# shupito.net
KiCad netlist of a schematic drawn in EAGLE
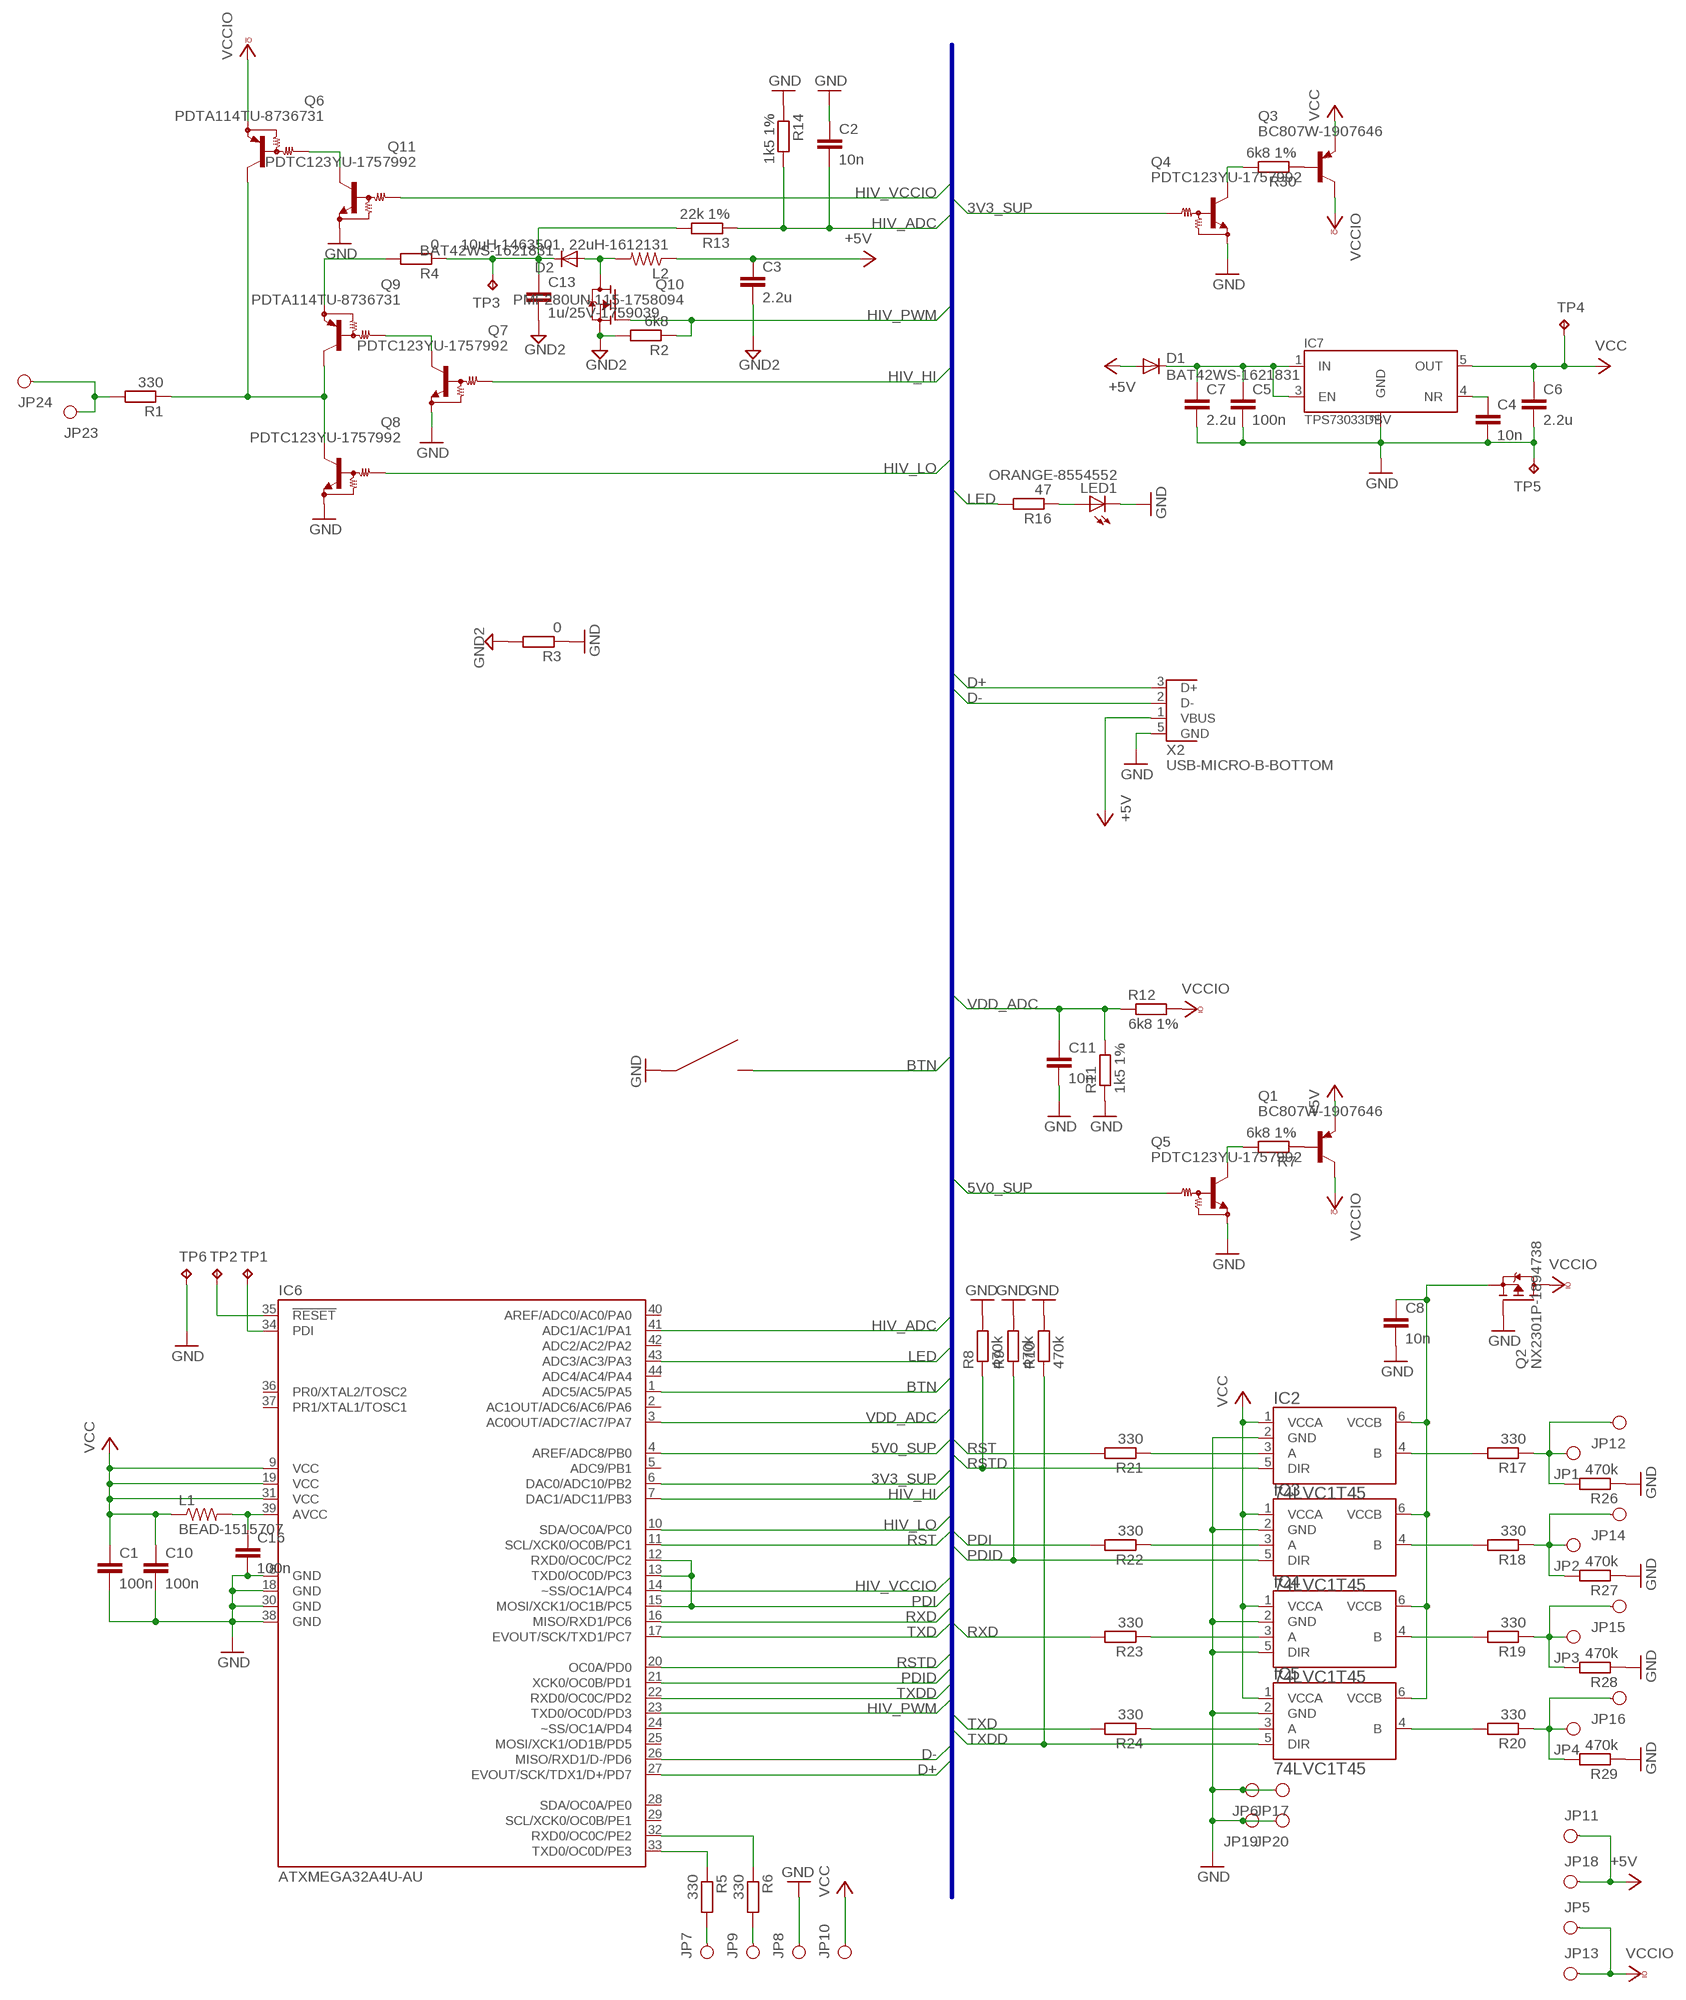
[diagram p0: schematic, sheet 1]

(export (version "E")
  (design (tool "Eeschema 10.0.6"))
  (components
    (comp (ref "C1")
      (value "100n")
      (footprint "eagle-import:C0603K")
      (libsource (lib "eagle-import") (part "C-EUC0603K"))
    )
    (comp (ref "C2")
      (value "10n")
      (footprint "eagle-import:C0603K")
      (libsource (lib "eagle-import") (part "C-EUC0603K"))
    )
    (comp (ref "C3")
      (value "2.2u")
      (footprint "eagle-import:C0603K")
      (libsource (lib "eagle-import") (part "C-EUC0603K"))
    )
    (comp (ref "C4")
      (value "10n")
      (footprint "eagle-import:C0603K")
      (libsource (lib "eagle-import") (part "C-EUC0603K"))
    )
    (comp (ref "C5")
      (value "100n")
      (footprint "eagle-import:C0603K")
      (libsource (lib "eagle-import") (part "C-EUC0603K"))
    )
    (comp (ref "C6")
      (value "2.2u")
      (footprint "eagle-import:C0603K")
      (libsource (lib "eagle-import") (part "C-EUC0603K"))
    )
    (comp (ref "C7")
      (value "2.2u")
      (footprint "eagle-import:C0603K")
      (libsource (lib "eagle-import") (part "C-EUC0603K"))
    )
    (comp (ref "C8")
      (value "10n")
      (footprint "eagle-import:C0603K")
      (libsource (lib "eagle-import") (part "C-EUC0603K"))
    )
    (comp (ref "C10")
      (value "100n")
      (footprint "eagle-import:C0603K")
      (libsource (lib "eagle-import") (part "C-EUC0603K"))
    )
    (comp (ref "C11")
      (value "10n")
      (footprint "eagle-import:C0603K")
      (libsource (lib "eagle-import") (part "C-EUC0603K"))
    )
    (comp (ref "C13")
      (value "1u/25V-1759039")
      (footprint "eagle-import:C0603K")
      (libsource (lib "eagle-import") (part "C-EUC0603K"))
    )
    (comp (ref "C16")
      (value "100n")
      (footprint "eagle-import:C0603K")
      (libsource (lib "eagle-import") (part "C-EUC0603K"))
    )
    (comp (ref "D1")
      (value "BAT42WS-1621831")
      (footprint "eagle-import:SOD323")
      (libsource (lib "eagle-import") (part "DIODE-SOD323"))
    )
    (comp (ref "D2")
      (value "BAT42WS-1621831")
      (footprint "eagle-import:SOD323")
      (libsource (lib "eagle-import") (part "DIODE-SOD323"))
    )
    (comp (ref "IC2")
      (value "74LVC1T45")
      (footprint "eagle-import:SOT236")
      (libsource (lib "eagle-import") (part "741T45DBVLVC"))
    )
    (comp (ref "IC3")
      (value "74LVC1T45")
      (footprint "eagle-import:SOT236")
      (libsource (lib "eagle-import") (part "741T45DBVLVC"))
    )
    (comp (ref "IC4")
      (value "74LVC1T45")
      (footprint "eagle-import:SOT236")
      (libsource (lib "eagle-import") (part "741T45DBVLVC"))
    )
    (comp (ref "IC5")
      (value "74LVC1T45")
      (footprint "eagle-import:SOT236")
      (libsource (lib "eagle-import") (part "741T45DBVLVC"))
    )
    (comp (ref "IC6")
      (value "ATXMEGA32A4U-AU")
      (footprint "eagle-import:TQFP44")
      (libsource (lib "eagle-import") (part "ATXMEGAA4U-AU32"))
    )
    (comp (ref "IC7")
      (value "TPS73033DBV")
      (footprint "eagle-import:SOT23-DBV")
      (libsource (lib "eagle-import") (part "TPS73033DBV"))
    )
    (comp (ref "JP1")
      (value "PINH1X01SMD")
      (footprint "eagle-import:PINH1X01SMD")
      (libsource (lib "eagle-import") (part "PINH1X01SMD"))
    )
    (comp (ref "JP2")
      (value "PINH1X01SMD")
      (footprint "eagle-import:PINH1X01SMD")
      (libsource (lib "eagle-import") (part "PINH1X01SMD"))
    )
    (comp (ref "JP3")
      (value "PINH1X01SMD")
      (footprint "eagle-import:PINH1X01SMD")
      (libsource (lib "eagle-import") (part "PINH1X01SMD"))
    )
    (comp (ref "JP4")
      (value "PINH1X01SMD")
      (footprint "eagle-import:PINH1X01SMD")
      (libsource (lib "eagle-import") (part "PINH1X01SMD"))
    )
    (comp (ref "JP5")
      (value "PINH1X01SMD")
      (footprint "eagle-import:PINH1X01SMD")
      (libsource (lib "eagle-import") (part "PINH1X01SMD"))
    )
    (comp (ref "JP6")
      (value "PINH1X01SMD")
      (footprint "eagle-import:PINH1X01SMD")
      (libsource (lib "eagle-import") (part "PINH1X01SMD"))
    )
    (comp (ref "JP7")
      (value "PINH1X01SMD")
      (footprint "eagle-import:PINH1X01SMD")
      (libsource (lib "eagle-import") (part "PINH1X01SMD"))
    )
    (comp (ref "JP8")
      (value "PINH1X01SMD")
      (footprint "eagle-import:PINH1X01SMD")
      (libsource (lib "eagle-import") (part "PINH1X01SMD"))
    )
    (comp (ref "JP9")
      (value "PINH1X01SMD")
      (footprint "eagle-import:PINH1X01SMD")
      (libsource (lib "eagle-import") (part "PINH1X01SMD"))
    )
    (comp (ref "JP10")
      (value "PINH1X01SMD")
      (footprint "eagle-import:PINH1X01SMD")
      (libsource (lib "eagle-import") (part "PINH1X01SMD"))
    )
    (comp (ref "JP11")
      (value "PINH1X01SMD")
      (footprint "eagle-import:PINH1X01SMD")
      (libsource (lib "eagle-import") (part "PINH1X01SMD"))
    )
    (comp (ref "JP12")
      (value "PINH1X01SMD")
      (footprint "eagle-import:PINH1X01SMD")
      (libsource (lib "eagle-import") (part "PINH1X01SMD"))
    )
    (comp (ref "JP13")
      (value "PINH1X01SMD")
      (footprint "eagle-import:PINH1X01SMD")
      (libsource (lib "eagle-import") (part "PINH1X01SMD"))
    )
    (comp (ref "JP14")
      (value "PINH1X01SMD")
      (footprint "eagle-import:PINH1X01SMD")
      (libsource (lib "eagle-import") (part "PINH1X01SMD"))
    )
    (comp (ref "JP15")
      (value "PINH1X01SMD")
      (footprint "eagle-import:PINH1X01SMD")
      (libsource (lib "eagle-import") (part "PINH1X01SMD"))
    )
    (comp (ref "JP16")
      (value "PINH1X01SMD")
      (footprint "eagle-import:PINH1X01SMD")
      (libsource (lib "eagle-import") (part "PINH1X01SMD"))
    )
    (comp (ref "JP17")
      (value "PINH1X01SMD")
      (footprint "eagle-import:PINH1X01SMD")
      (libsource (lib "eagle-import") (part "PINH1X01SMD"))
    )
    (comp (ref "JP18")
      (value "PINH1X01SMD")
      (footprint "eagle-import:PINH1X01SMD")
      (libsource (lib "eagle-import") (part "PINH1X01SMD"))
    )
    (comp (ref "JP19")
      (value "PINH1X01SMD")
      (footprint "eagle-import:PINH1X01SMD")
      (libsource (lib "eagle-import") (part "PINH1X01SMD"))
    )
    (comp (ref "JP20")
      (value "PINH1X01SMD")
      (footprint "eagle-import:PINH1X01SMD")
      (libsource (lib "eagle-import") (part "PINH1X01SMD"))
    )
    (comp (ref "JP23")
      (value "PINH1X01SMD")
      (footprint "eagle-import:PINH1X01SMD")
      (libsource (lib "eagle-import") (part "PINH1X01SMD"))
    )
    (comp (ref "JP24")
      (value "PINH1X01SMD")
      (footprint "eagle-import:PINH1X01SMD")
      (libsource (lib "eagle-import") (part "PINH1X01SMD"))
    )
    (comp (ref "L1")
      (value "BEAD-1515707")
      (footprint "eagle-import:R0603")
      (libsource (lib "eagle-import") (part "R-US_R0603"))
    )
    (comp (ref "L2")
      (value "10uH-1463501, 22uH-1612131")
      (footprint "eagle-import:R0805")
      (libsource (lib "eagle-import") (part "R-US_R0805"))
    )
    (comp (ref "LED1")
      (value "ORANGE-8554552")
      (footprint "eagle-import:CHIPLED_0603")
      (libsource (lib "eagle-import") (part "LEDCHIPLED_0603"))
    )
    (comp (ref "Q1")
      (value "BC807W-1907646")
      (footprint "eagle-import:SOT323-BEC")
      (libsource (lib "eagle-import") (part "BC807W"))
    )
    (comp (ref "Q2")
      (value "NX2301P-1894738")
      (footprint "eagle-import:SOT23")
      (libsource (lib "eagle-import") (part "P-MOSFET-SOT23-GSD"))
    )
    (comp (ref "Q3")
      (value "BC807W-1907646")
      (footprint "eagle-import:SOT323-BEC")
      (libsource (lib "eagle-import") (part "BC807W"))
    )
    (comp (ref "Q4")
      (value "PDTC123YU-1757992")
      (footprint "eagle-import:SOT323")
      (libsource (lib "eagle-import") (part "NPN-BIAS-SOT323-BEC"))
    )
    (comp (ref "Q5")
      (value "PDTC123YU-1757992")
      (footprint "eagle-import:SOT323")
      (libsource (lib "eagle-import") (part "NPN-BIAS-SOT323-BEC"))
    )
    (comp (ref "Q6")
      (value "PDTA114TU-8736731")
      (footprint "eagle-import:SOT323")
      (libsource (lib "eagle-import") (part "PNP-BIAS-SOT323-BEC"))
    )
    (comp (ref "Q7")
      (value "PDTC123YU-1757992")
      (footprint "eagle-import:SOT323")
      (libsource (lib "eagle-import") (part "NPN-BIAS-SOT323-BEC"))
    )
    (comp (ref "Q8")
      (value "PDTC123YU-1757992")
      (footprint "eagle-import:SOT323")
      (libsource (lib "eagle-import") (part "NPN-BIAS-SOT323-BEC"))
    )
    (comp (ref "Q9")
      (value "PDTA114TU-8736731")
      (footprint "eagle-import:SOT323")
      (libsource (lib "eagle-import") (part "PNP-BIAS-SOT323-BEC"))
    )
    (comp (ref "Q10")
      (value "PMF280UN,115-1758094")
      (footprint "eagle-import:SOT323")
      (libsource (lib "eagle-import") (part "N-MOSFET-SOT323-GSD"))
    )
    (comp (ref "Q11")
      (value "PDTC123YU-1757992")
      (footprint "eagle-import:SOT323")
      (libsource (lib "eagle-import") (part "NPN-BIAS-SOT323-BEC"))
    )
    (comp (ref "R1")
      (value "330")
      (footprint "eagle-import:R0603")
      (libsource (lib "eagle-import") (part "R-EU_R0603"))
    )
    (comp (ref "R2")
      (value "6k8")
      (footprint "eagle-import:R0603")
      (libsource (lib "eagle-import") (part "R-EU_R0603"))
    )
    (comp (ref "R3")
      (value "0")
      (footprint "eagle-import:R1206")
      (libsource (lib "eagle-import") (part "R-EU_R1206"))
    )
    (comp (ref "R4")
      (value "0")
      (footprint "eagle-import:R1206")
      (libsource (lib "eagle-import") (part "R-EU_R1206"))
    )
    (comp (ref "R5")
      (value "330")
      (footprint "eagle-import:R0603")
      (libsource (lib "eagle-import") (part "R-EU_R0603"))
    )
    (comp (ref "R6")
      (value "330")
      (footprint "eagle-import:R0603")
      (libsource (lib "eagle-import") (part "R-EU_R0603"))
    )
    (comp (ref "R7")
      (value "6k8 1%")
      (footprint "eagle-import:R0603")
      (libsource (lib "eagle-import") (part "R-EU_R0603"))
    )
    (comp (ref "R8")
      (value "470k")
      (footprint "eagle-import:R0603")
      (libsource (lib "eagle-import") (part "R-EU_R0603"))
    )
    (comp (ref "R9")
      (value "470k")
      (footprint "eagle-import:R0603")
      (libsource (lib "eagle-import") (part "R-EU_R0603"))
    )
    (comp (ref "R10")
      (value "470k")
      (footprint "eagle-import:R0603")
      (libsource (lib "eagle-import") (part "R-EU_R0603"))
    )
    (comp (ref "R11")
      (value "1k5 1%")
      (footprint "eagle-import:R0603")
      (libsource (lib "eagle-import") (part "R-EU_R0603"))
    )
    (comp (ref "R12")
      (value "6k8 1%")
      (footprint "eagle-import:R0603")
      (libsource (lib "eagle-import") (part "R-EU_R0603"))
    )
    (comp (ref "R13")
      (value "22k 1%")
      (footprint "eagle-import:R0603")
      (libsource (lib "eagle-import") (part "R-EU_R0603"))
    )
    (comp (ref "R14")
      (value "1k5 1%")
      (footprint "eagle-import:R0603")
      (libsource (lib "eagle-import") (part "R-EU_R0603"))
    )
    (comp (ref "R16")
      (value "47")
      (footprint "eagle-import:R0603")
      (libsource (lib "eagle-import") (part "R-EU_R0603"))
    )
    (comp (ref "R17")
      (value "330")
      (footprint "eagle-import:R0603")
      (libsource (lib "eagle-import") (part "R-EU_R0603"))
    )
    (comp (ref "R18")
      (value "330")
      (footprint "eagle-import:R0603")
      (libsource (lib "eagle-import") (part "R-EU_R0603"))
    )
    (comp (ref "R19")
      (value "330")
      (footprint "eagle-import:R0603")
      (libsource (lib "eagle-import") (part "R-EU_R0603"))
    )
    (comp (ref "R20")
      (value "330")
      (footprint "eagle-import:R0603")
      (libsource (lib "eagle-import") (part "R-EU_R0603"))
    )
    (comp (ref "R21")
      (value "330")
      (footprint "eagle-import:R0603")
      (libsource (lib "eagle-import") (part "R-EU_R0603"))
    )
    (comp (ref "R22")
      (value "330")
      (footprint "eagle-import:R0603")
      (libsource (lib "eagle-import") (part "R-EU_R0603"))
    )
    (comp (ref "R23")
      (value "330")
      (footprint "eagle-import:R0603")
      (libsource (lib "eagle-import") (part "R-EU_R0603"))
    )
    (comp (ref "R24")
      (value "330")
      (footprint "eagle-import:R0603")
      (libsource (lib "eagle-import") (part "R-EU_R0603"))
    )
    (comp (ref "R26")
      (value "470k")
      (footprint "eagle-import:R0603")
      (libsource (lib "eagle-import") (part "R-EU_R0603"))
    )
    (comp (ref "R27")
      (value "470k")
      (footprint "eagle-import:R0603")
      (libsource (lib "eagle-import") (part "R-EU_R0603"))
    )
    (comp (ref "R28")
      (value "470k")
      (footprint "eagle-import:R0603")
      (libsource (lib "eagle-import") (part "R-EU_R0603"))
    )
    (comp (ref "R29")
      (value "470k")
      (footprint "eagle-import:R0603")
      (libsource (lib "eagle-import") (part "R-EU_R0603"))
    )
    (comp (ref "R30")
      (value "6k8 1%")
      (footprint "eagle-import:R0603")
      (libsource (lib "eagle-import") (part "R-EU_R0603"))
    )
    (comp (ref "S1")
      (value "KSS241G")
      (footprint "eagle-import:KSS-G")
      (libsource (lib "eagle-import") (part "KSSG241"))
    )
    (comp (ref "TP1")
      (value "TPTP15SQ")
      (footprint "eagle-import:TP15SQ")
      (libsource (lib "eagle-import") (part "TPTP15SQ"))
    )
    (comp (ref "TP2")
      (value "TPTP15SQ")
      (footprint "eagle-import:TP15SQ")
      (libsource (lib "eagle-import") (part "TPTP15SQ"))
    )
    (comp (ref "TP3")
      (value "TPTP15SQ")
      (footprint "eagle-import:TP15SQ")
      (libsource (lib "eagle-import") (part "TPTP15SQ"))
    )
    (comp (ref "TP4")
      (value "TPTP15SQ")
      (footprint "eagle-import:TP15SQ")
      (libsource (lib "eagle-import") (part "TPTP15SQ"))
    )
    (comp (ref "TP5")
      (value "TPTP15SQ")
      (footprint "eagle-import:TP15SQ")
      (libsource (lib "eagle-import") (part "TPTP15SQ"))
    )
    (comp (ref "TP6")
      (value "TPTP15SQ")
      (footprint "eagle-import:TP15SQ")
      (libsource (lib "eagle-import") (part "TPTP15SQ"))
    )
    (comp (ref "X2")
      (value "USB-MICRO-B-BOTTOM")
      (footprint "eagle-import:USB-MICRO-B-BOTTOM-MOLEX")
      (libsource (lib "eagle-import") (part "USB-MICRO-B-BOTTOM"))
    )
  )
  (nets
    (net (code "1") (name "+5V") (class "Default")
      (node (ref "C3") (pin "1") (pinfunction "1_1") (pintype "passive"))
      (node (ref "D1") (pin "A") (pinfunction "A_A") (pintype "passive"))
      (node (ref "JP11") (pin "1") (pinfunction "1_1") (pintype "passive"))
      (node (ref "JP18") (pin "1") (pinfunction "1_1") (pintype "passive"))
      (node (ref "L2") (pin "1") (pinfunction "1_1") (pintype "passive"))
      (node (ref "Q1") (pin "2") (pinfunction "E_2") (pintype "passive"))
      (node (ref "X2") (pin "1") (pinfunction "VBUS_1") (pintype "passive"))
    )
    (net (code "2") (name "/3V3_SUP") (class "Default")
      (node (ref "IC6") (pin "6") (pinfunction "DAC0/ADC10/PB2_6") (pintype "bidirectional"))
      (node (ref "Q4") (pin "1") (pinfunction "B_1") (pintype "passive"))
    )
    (net (code "3") (name "/5V0_SUP") (class "Default")
      (node (ref "IC6") (pin "4") (pinfunction "AREF/ADC8/PB0_4") (pintype "bidirectional"))
      (node (ref "Q5") (pin "1") (pinfunction "B_1") (pintype "passive"))
    )
    (net (code "4") (name "/BTN") (class "Default")
      (node (ref "IC6") (pin "1") (pinfunction "ADC5/AC5/PA5_1") (pintype "bidirectional"))
      (node (ref "S1") (pin "2") (pinfunction "P$2_2") (pintype "passive"))
    )
    (net (code "5") (name "/D+") (class "Default")
      (node (ref "IC6") (pin "27") (pinfunction "EVOUT/SCK/TDX1/D+/PD7_27") (pintype "bidirectional"))
      (node (ref "X2") (pin "3") (pinfunction "D+_3") (pintype "bidirectional"))
    )
    (net (code "6") (name "/D-") (class "Default")
      (node (ref "IC6") (pin "26") (pinfunction "MISO/RXD1/D-/PD6_26") (pintype "bidirectional"))
      (node (ref "X2") (pin "2") (pinfunction "D-_2") (pintype "bidirectional"))
    )
    (net (code "7") (name "/HIV_ADC") (class "Default")
      (node (ref "C2") (pin "2") (pinfunction "2_2") (pintype "passive"))
      (node (ref "IC6") (pin "41") (pinfunction "ADC1/AC1/PA1_41") (pintype "bidirectional"))
      (node (ref "R13") (pin "1") (pinfunction "1_1") (pintype "passive"))
      (node (ref "R14") (pin "2") (pinfunction "2_2") (pintype "passive"))
    )
    (net (code "8") (name "/HIV_HI") (class "Default")
      (node (ref "IC6") (pin "7") (pinfunction "DAC1/ADC11/PB3_7") (pintype "bidirectional"))
      (node (ref "Q7") (pin "1") (pinfunction "B_1") (pintype "passive"))
    )
    (net (code "9") (name "/HIV_LO") (class "Default")
      (node (ref "IC6") (pin "10") (pinfunction "SDA/OC0A/PC0_10") (pintype "bidirectional"))
      (node (ref "Q8") (pin "1") (pinfunction "B_1") (pintype "passive"))
    )
    (net (code "10") (name "/HIV_PWM") (class "Default")
      (node (ref "IC6") (pin "23") (pinfunction "TXD0/OC0D/PD3_23") (pintype "bidirectional"))
      (node (ref "Q10") (pin "1") (pinfunction "G_1") (pintype "passive"))
      (node (ref "R2") (pin "1") (pinfunction "1_1") (pintype "passive"))
    )
    (net (code "11") (name "/HIV_VCCIO") (class "Default")
      (node (ref "IC6") (pin "14") (pinfunction "~{SS/OC1A/PC4}_14") (pintype "bidirectional"))
      (node (ref "Q11") (pin "1") (pinfunction "B_1") (pintype "passive"))
    )
    (net (code "12") (name "/LED") (class "Default")
      (node (ref "IC6") (pin "43") (pinfunction "ADC3/AC3/PA3_43") (pintype "bidirectional"))
      (node (ref "R16") (pin "2") (pinfunction "2_2") (pintype "passive"))
    )
    (net (code "13") (name "/PDI") (class "Default")
      (node (ref "IC6") (pin "12") (pinfunction "RXD0/OC0C/PC2_12") (pintype "bidirectional"))
      (node (ref "IC6") (pin "13") (pinfunction "TXD0/OC0D/PC3_13") (pintype "bidirectional"))
      (node (ref "IC6") (pin "15") (pinfunction "MOSI/XCK1/OC1B/PC5_15") (pintype "bidirectional"))
      (node (ref "R22") (pin "2") (pinfunction "2_2") (pintype "passive"))
    )
    (net (code "14") (name "/PDID") (class "Default")
      (node (ref "IC3") (pin "5") (pinfunction "DIR_5") (pintype "input"))
      (node (ref "IC6") (pin "21") (pinfunction "XCK0/OC0B/PD1_21") (pintype "bidirectional"))
      (node (ref "R9") (pin "1") (pinfunction "1_1") (pintype "passive"))
    )
    (net (code "15") (name "/RST") (class "Default")
      (node (ref "IC6") (pin "11") (pinfunction "SCL/XCK0/OC0B/PC1_11") (pintype "bidirectional"))
      (node (ref "R21") (pin "2") (pinfunction "2_2") (pintype "passive"))
    )
    (net (code "16") (name "/RSTD") (class "Default")
      (node (ref "IC2") (pin "5") (pinfunction "DIR_5") (pintype "input"))
      (node (ref "IC6") (pin "20") (pinfunction "OC0A/PD0_20") (pintype "bidirectional"))
      (node (ref "R8") (pin "1") (pinfunction "1_1") (pintype "passive"))
    )
    (net (code "17") (name "/RXD") (class "Default")
      (node (ref "IC6") (pin "16") (pinfunction "MISO/RXD1/PC6_16") (pintype "bidirectional"))
      (node (ref "R23") (pin "2") (pinfunction "2_2") (pintype "passive"))
    )
    (net (code "18") (name "/TXD") (class "Default")
      (node (ref "IC6") (pin "17") (pinfunction "EVOUT/SCK/TXD1/PC7_17") (pintype "bidirectional"))
      (node (ref "R24") (pin "2") (pinfunction "2_2") (pintype "passive"))
    )
    (net (code "19") (name "/TXDD") (class "Default")
      (node (ref "IC5") (pin "5") (pinfunction "DIR_5") (pintype "input"))
      (node (ref "IC6") (pin "22") (pinfunction "RXD0/OC0C/PD2_22") (pintype "bidirectional"))
      (node (ref "R10") (pin "1") (pinfunction "1_1") (pintype "passive"))
    )
    (net (code "20") (name "/VDD_ADC") (class "Default")
      (node (ref "C11") (pin "1") (pinfunction "1_1") (pintype "passive"))
      (node (ref "IC6") (pin "3") (pinfunction "AC0OUT/ADC7/AC7/PA7_3") (pintype "bidirectional"))
      (node (ref "R11") (pin "2") (pinfunction "2_2") (pintype "passive"))
      (node (ref "R12") (pin "1") (pinfunction "1_1") (pintype "passive"))
    )
    (net (code "21") (name "GND") (class "Default")
      (node (ref "C1") (pin "2") (pinfunction "2_2") (pintype "passive"))
      (node (ref "C10") (pin "2") (pinfunction "2_2") (pintype "passive"))
      (node (ref "C11") (pin "2") (pinfunction "2_2") (pintype "passive"))
      (node (ref "C16") (pin "2") (pinfunction "2_2") (pintype "passive"))
      (node (ref "C2") (pin "1") (pinfunction "1_1") (pintype "passive"))
      (node (ref "C4") (pin "2") (pinfunction "2_2") (pintype "passive"))
      (node (ref "C5") (pin "2") (pinfunction "2_2") (pintype "passive"))
      (node (ref "C6") (pin "2") (pinfunction "2_2") (pintype "passive"))
      (node (ref "C7") (pin "2") (pinfunction "2_2") (pintype "passive"))
      (node (ref "C8") (pin "2") (pinfunction "2_2") (pintype "passive"))
      (node (ref "IC2") (pin "2") (pinfunction "GND_2") (pintype "passive"))
      (node (ref "IC3") (pin "2") (pinfunction "GND_2") (pintype "passive"))
      (node (ref "IC4") (pin "2") (pinfunction "GND_2") (pintype "passive"))
      (node (ref "IC4") (pin "5") (pinfunction "DIR_5") (pintype "input"))
      (node (ref "IC5") (pin "2") (pinfunction "GND_2") (pintype "passive"))
      (node (ref "IC6") (pin "18") (pinfunction "GND_18") (pintype "passive"))
      (node (ref "IC6") (pin "30") (pinfunction "GND_30") (pintype "passive"))
      (node (ref "IC6") (pin "38") (pinfunction "GND_38") (pintype "passive"))
      (node (ref "IC6") (pin "8") (pinfunction "GND_8") (pintype "passive"))
      (node (ref "IC7") (pin "2") (pinfunction "GND_2") (pintype "passive"))
      (node (ref "JP17") (pin "1") (pinfunction "1_1") (pintype "passive"))
      (node (ref "JP19") (pin "1") (pinfunction "1_1") (pintype "passive"))
      (node (ref "JP20") (pin "1") (pinfunction "1_1") (pintype "passive"))
      (node (ref "JP6") (pin "1") (pinfunction "1_1") (pintype "passive"))
      (node (ref "JP8") (pin "1") (pinfunction "1_1") (pintype "passive"))
      (node (ref "LED1") (pin "C") (pinfunction "C_C") (pintype "passive"))
      (node (ref "Q11") (pin "2") (pinfunction "E_2") (pintype "passive"))
      (node (ref "Q2") (pin "1") (pinfunction "G_1") (pintype "passive"))
      (node (ref "Q4") (pin "2") (pinfunction "E_2") (pintype "passive"))
      (node (ref "Q5") (pin "2") (pinfunction "E_2") (pintype "passive"))
      (node (ref "Q7") (pin "2") (pinfunction "E_2") (pintype "passive"))
      (node (ref "Q8") (pin "2") (pinfunction "E_2") (pintype "passive"))
      (node (ref "R10") (pin "2") (pinfunction "2_2") (pintype "passive"))
      (node (ref "R11") (pin "1") (pinfunction "1_1") (pintype "passive"))
      (node (ref "R14") (pin "1") (pinfunction "1_1") (pintype "passive"))
      (node (ref "R26") (pin "1") (pinfunction "1_1") (pintype "passive"))
      (node (ref "R27") (pin "1") (pinfunction "1_1") (pintype "passive"))
      (node (ref "R28") (pin "1") (pinfunction "1_1") (pintype "passive"))
      (node (ref "R29") (pin "1") (pinfunction "1_1") (pintype "passive"))
      (node (ref "R3") (pin "1") (pinfunction "1_1") (pintype "passive"))
      (node (ref "R8") (pin "2") (pinfunction "2_2") (pintype "passive"))
      (node (ref "R9") (pin "2") (pinfunction "2_2") (pintype "passive"))
      (node (ref "S1") (pin "1") (pinfunction "P$1_1") (pintype "passive"))
      (node (ref "TP5") (pin "TP") (pinfunction "TP_TP") (pintype "input"))
      (node (ref "TP6") (pin "TP") (pinfunction "TP_TP") (pintype "input"))
      (node (ref "X2") (pin "5") (pinfunction "GND_5") (pintype "passive"))
    )
    (net (code "22") (name "GND2") (class "Default")
      (node (ref "C13") (pin "2") (pinfunction "2_2") (pintype "passive"))
      (node (ref "C3") (pin "2") (pinfunction "2_2") (pintype "passive"))
      (node (ref "Q10") (pin "2") (pinfunction "S_2") (pintype "passive"))
      (node (ref "R2") (pin "2") (pinfunction "2_2") (pintype "passive"))
      (node (ref "R3") (pin "2") (pinfunction "2_2") (pintype "passive"))
    )
    (net (code "23") (name "Net-(C13-Pad1)") (class "Default")
      (node (ref "C13") (pin "1") (pinfunction "1_1") (pintype "passive"))
      (node (ref "D2") (pin "C") (pinfunction "C_C") (pintype "passive"))
      (node (ref "R13") (pin "2") (pinfunction "2_2") (pintype "passive"))
      (node (ref "R4") (pin "1") (pinfunction "1_1") (pintype "passive"))
      (node (ref "TP3") (pin "TP") (pinfunction "TP_TP") (pintype "input"))
    )
    (net (code "24") (name "Net-(IC2-A)") (class "Default")
      (node (ref "IC2") (pin "3") (pinfunction "A_3") (pintype "bidirectional"))
      (node (ref "R21") (pin "1") (pinfunction "1_1") (pintype "passive"))
    )
    (net (code "25") (name "Net-(IC2-B)") (class "Default")
      (node (ref "IC2") (pin "4") (pinfunction "B_4") (pintype "bidirectional"))
      (node (ref "R17") (pin "2") (pinfunction "2_2") (pintype "passive"))
    )
    (net (code "26") (name "Net-(IC2-VCCB)") (class "Default")
      (node (ref "C8") (pin "1") (pinfunction "1_1") (pintype "passive"))
      (node (ref "IC2") (pin "6") (pinfunction "VCCB_6") (pintype "passive"))
      (node (ref "IC3") (pin "6") (pinfunction "VCCB_6") (pintype "passive"))
      (node (ref "IC4") (pin "6") (pinfunction "VCCB_6") (pintype "passive"))
      (node (ref "IC5") (pin "6") (pinfunction "VCCB_6") (pintype "passive"))
      (node (ref "Q2") (pin "2") (pinfunction "S_2") (pintype "passive"))
    )
    (net (code "27") (name "Net-(IC3-A)") (class "Default")
      (node (ref "IC3") (pin "3") (pinfunction "A_3") (pintype "bidirectional"))
      (node (ref "R22") (pin "1") (pinfunction "1_1") (pintype "passive"))
    )
    (net (code "28") (name "Net-(IC3-B)") (class "Default")
      (node (ref "IC3") (pin "4") (pinfunction "B_4") (pintype "bidirectional"))
      (node (ref "R18") (pin "2") (pinfunction "2_2") (pintype "passive"))
    )
    (net (code "29") (name "Net-(IC4-A)") (class "Default")
      (node (ref "IC4") (pin "3") (pinfunction "A_3") (pintype "bidirectional"))
      (node (ref "R23") (pin "1") (pinfunction "1_1") (pintype "passive"))
    )
    (net (code "30") (name "Net-(IC4-B)") (class "Default")
      (node (ref "IC4") (pin "4") (pinfunction "B_4") (pintype "bidirectional"))
      (node (ref "R19") (pin "2") (pinfunction "2_2") (pintype "passive"))
    )
    (net (code "31") (name "Net-(IC5-A)") (class "Default")
      (node (ref "IC5") (pin "3") (pinfunction "A_3") (pintype "bidirectional"))
      (node (ref "R24") (pin "1") (pinfunction "1_1") (pintype "passive"))
    )
    (net (code "32") (name "Net-(IC5-B)") (class "Default")
      (node (ref "IC5") (pin "4") (pinfunction "B_4") (pintype "bidirectional"))
      (node (ref "R20") (pin "2") (pinfunction "2_2") (pintype "passive"))
    )
    (net (code "33") (name "Net-(IC6-AVCC)") (class "Default")
      (node (ref "C16") (pin "1") (pinfunction "1_1") (pintype "passive"))
      (node (ref "IC6") (pin "39") (pinfunction "AVCC_39") (pintype "passive"))
      (node (ref "L1") (pin "2") (pinfunction "2_2") (pintype "passive"))
    )
    (net (code "34") (name "Net-(IC6-PDI)") (class "Default")
      (node (ref "IC6") (pin "34") (pinfunction "PDI_34") (pintype "bidirectional"))
      (node (ref "TP1") (pin "TP") (pinfunction "TP_TP") (pintype "input"))
    )
    (net (code "35") (name "Net-(IC6-RXD0{slash}OC0C{slash}PE2)") (class "Default")
      (node (ref "IC6") (pin "32") (pinfunction "RXD0/OC0C/PE2_32") (pintype "bidirectional"))
      (node (ref "R6") (pin "1") (pinfunction "1_1") (pintype "passive"))
    )
    (net (code "36") (name "Net-(IC6-TXD0{slash}OC0D{slash}PE3)") (class "Default")
      (node (ref "IC6") (pin "33") (pinfunction "TXD0/OC0D/PE3_33") (pintype "bidirectional"))
      (node (ref "R5") (pin "1") (pinfunction "1_1") (pintype "passive"))
    )
    (net (code "37") (name "Net-(IC6-~{RESET})") (class "Default")
      (node (ref "IC6") (pin "35") (pinfunction "~{RESET}_35") (pintype "input"))
      (node (ref "TP2") (pin "TP") (pinfunction "TP_TP") (pintype "input"))
    )
    (net (code "38") (name "Net-(IC7-EN)") (class "Default")
      (node (ref "C5") (pin "1") (pinfunction "1_1") (pintype "passive"))
      (node (ref "C7") (pin "1") (pinfunction "1_1") (pintype "passive"))
      (node (ref "D1") (pin "C") (pinfunction "C_C") (pintype "passive"))
      (node (ref "IC7") (pin "1") (pinfunction "IN_1") (pintype "passive"))
      (node (ref "IC7") (pin "3") (pinfunction "EN_3") (pintype "input"))
    )
    (net (code "39") (name "Net-(IC7-NR)") (class "Default")
      (node (ref "C4") (pin "1") (pinfunction "1_1") (pintype "passive"))
      (node (ref "IC7") (pin "4") (pinfunction "NR_4") (pintype "passive"))
    )
    (net (code "40") (name "Net-(JP1-Pad1)") (class "Default")
      (node (ref "JP1") (pin "1") (pinfunction "1_1") (pintype "passive"))
      (node (ref "JP12") (pin "1") (pinfunction "1_1") (pintype "passive"))
      (node (ref "R17") (pin "1") (pinfunction "1_1") (pintype "passive"))
      (node (ref "R26") (pin "2") (pinfunction "2_2") (pintype "passive"))
    )
    (net (code "41") (name "Net-(JP7-Pad1)") (class "Default")
      (node (ref "JP7") (pin "1") (pinfunction "1_1") (pintype "passive"))
      (node (ref "R5") (pin "2") (pinfunction "2_2") (pintype "passive"))
    )
    (net (code "42") (name "Net-(JP9-Pad1)") (class "Default")
      (node (ref "JP9") (pin "1") (pinfunction "1_1") (pintype "passive"))
      (node (ref "R6") (pin "2") (pinfunction "2_2") (pintype "passive"))
    )
    (net (code "43") (name "Net-(JP14-Pad1)") (class "Default")
      (node (ref "JP14") (pin "1") (pinfunction "1_1") (pintype "passive"))
      (node (ref "JP2") (pin "1") (pinfunction "1_1") (pintype "passive"))
      (node (ref "R18") (pin "1") (pinfunction "1_1") (pintype "passive"))
      (node (ref "R27") (pin "2") (pinfunction "2_2") (pintype "passive"))
    )
    (net (code "44") (name "Net-(JP15-Pad1)") (class "Default")
      (node (ref "JP15") (pin "1") (pinfunction "1_1") (pintype "passive"))
      (node (ref "JP3") (pin "1") (pinfunction "1_1") (pintype "passive"))
      (node (ref "R19") (pin "1") (pinfunction "1_1") (pintype "passive"))
      (node (ref "R28") (pin "2") (pinfunction "2_2") (pintype "passive"))
    )
    (net (code "45") (name "Net-(JP16-Pad1)") (class "Default")
      (node (ref "JP16") (pin "1") (pinfunction "1_1") (pintype "passive"))
      (node (ref "JP4") (pin "1") (pinfunction "1_1") (pintype "passive"))
      (node (ref "R20") (pin "1") (pinfunction "1_1") (pintype "passive"))
      (node (ref "R29") (pin "2") (pinfunction "2_2") (pintype "passive"))
    )
    (net (code "46") (name "Net-(JP23-Pad1)") (class "Default")
      (node (ref "JP23") (pin "1") (pinfunction "1_1") (pintype "passive"))
      (node (ref "JP24") (pin "1") (pinfunction "1_1") (pintype "passive"))
      (node (ref "R1") (pin "2") (pinfunction "2_2") (pintype "passive"))
    )
    (net (code "47") (name "Net-(LED1-PadA)") (class "Default")
      (node (ref "LED1") (pin "A") (pinfunction "A_A") (pintype "passive"))
      (node (ref "R16") (pin "1") (pinfunction "1_1") (pintype "passive"))
    )
    (net (code "48") (name "Net-(Q1-B)") (class "Default")
      (node (ref "Q1") (pin "1") (pinfunction "B_1") (pintype "passive"))
      (node (ref "R7") (pin "1") (pinfunction "1_1") (pintype "passive"))
    )
    (net (code "49") (name "Net-(Q3-B)") (class "Default")
      (node (ref "Q3") (pin "1") (pinfunction "B_1") (pintype "passive"))
      (node (ref "R30") (pin "1") (pinfunction "1_1") (pintype "passive"))
    )
    (net (code "50") (name "Net-(Q4-C)") (class "Default")
      (node (ref "Q4") (pin "3") (pinfunction "C_3") (pintype "passive"))
      (node (ref "R30") (pin "2") (pinfunction "2_2") (pintype "passive"))
    )
    (net (code "51") (name "Net-(Q5-C)") (class "Default")
      (node (ref "Q5") (pin "3") (pinfunction "C_3") (pintype "passive"))
      (node (ref "R7") (pin "2") (pinfunction "2_2") (pintype "passive"))
    )
    (net (code "52") (name "Net-(Q6-C)") (class "Default")
      (node (ref "Q6") (pin "3") (pinfunction "C_3") (pintype "passive"))
      (node (ref "Q8") (pin "3") (pinfunction "C_3") (pintype "passive"))
      (node (ref "Q9") (pin "3") (pinfunction "C_3") (pintype "passive"))
      (node (ref "R1") (pin "1") (pinfunction "1_1") (pintype "passive"))
    )
    (net (code "53") (name "Net-(Q7-C)") (class "Default")
      (node (ref "Q7") (pin "3") (pinfunction "C_3") (pintype "passive"))
      (node (ref "Q9") (pin "1") (pinfunction "B_1") (pintype "passive"))
    )
    (net (code "54") (name "Net-(Q9-E)") (class "Default")
      (node (ref "Q9") (pin "2") (pinfunction "E_2") (pintype "passive"))
      (node (ref "R4") (pin "2") (pinfunction "2_2") (pintype "passive"))
    )
    (net (code "55") (name "Net-(Q10-D)") (class "Default")
      (node (ref "D2") (pin "A") (pinfunction "A_A") (pintype "passive"))
      (node (ref "L2") (pin "2") (pinfunction "2_2") (pintype "passive"))
      (node (ref "Q10") (pin "3") (pinfunction "D_3") (pintype "passive"))
    )
    (net (code "56") (name "Net-(Q11-C)") (class "Default")
      (node (ref "Q11") (pin "3") (pinfunction "C_3") (pintype "passive"))
      (node (ref "Q6") (pin "1") (pinfunction "B_1") (pintype "passive"))
    )
    (net (code "57") (name "VCC") (class "Default")
      (node (ref "C1") (pin "1") (pinfunction "1_1") (pintype "passive"))
      (node (ref "C10") (pin "1") (pinfunction "1_1") (pintype "passive"))
      (node (ref "C6") (pin "1") (pinfunction "1_1") (pintype "passive"))
      (node (ref "IC2") (pin "1") (pinfunction "VCCA_1") (pintype "passive"))
      (node (ref "IC3") (pin "1") (pinfunction "VCCA_1") (pintype "passive"))
      (node (ref "IC4") (pin "1") (pinfunction "VCCA_1") (pintype "passive"))
      (node (ref "IC5") (pin "1") (pinfunction "VCCA_1") (pintype "passive"))
      (node (ref "IC6") (pin "19") (pinfunction "VCC_19") (pintype "passive"))
      (node (ref "IC6") (pin "31") (pinfunction "VCC_31") (pintype "passive"))
      (node (ref "IC6") (pin "9") (pinfunction "VCC_9") (pintype "passive"))
      (node (ref "IC7") (pin "5") (pinfunction "OUT_5") (pintype "passive"))
      (node (ref "JP10") (pin "1") (pinfunction "1_1") (pintype "passive"))
      (node (ref "L1") (pin "1") (pinfunction "1_1") (pintype "passive"))
      (node (ref "Q3") (pin "2") (pinfunction "E_2") (pintype "passive"))
      (node (ref "TP4") (pin "TP") (pinfunction "TP_TP") (pintype "input"))
    )
    (net (code "58") (name "VCCIO") (class "Default")
      (node (ref "JP13") (pin "1") (pinfunction "1_1") (pintype "passive"))
      (node (ref "JP5") (pin "1") (pinfunction "1_1") (pintype "passive"))
      (node (ref "Q1") (pin "3") (pinfunction "C_3") (pintype "passive"))
      (node (ref "Q2") (pin "3") (pinfunction "D_3") (pintype "passive"))
      (node (ref "Q3") (pin "3") (pinfunction "C_3") (pintype "passive"))
      (node (ref "Q6") (pin "2") (pinfunction "E_2") (pintype "passive"))
      (node (ref "R12") (pin "2") (pinfunction "2_2") (pintype "passive"))
    )
    (net (code "59") (name "unconnected-(IC6-AC1OUT{slash}ADC6{slash}AC6{slash}PA6-Pad2)") (class "Default")
      (node (ref "IC6") (pin "2") (pinfunction "AC1OUT/ADC6/AC6/PA6_2") (pintype "bidirectional"))
    )
    (net (code "60") (name "unconnected-(IC6-ADC2{slash}AC2{slash}PA2-Pad42)") (class "Default")
      (node (ref "IC6") (pin "42") (pinfunction "ADC2/AC2/PA2_42") (pintype "bidirectional"))
    )
    (net (code "61") (name "unconnected-(IC6-ADC4{slash}AC4{slash}PA4-Pad44)") (class "Default")
      (node (ref "IC6") (pin "44") (pinfunction "ADC4/AC4/PA4_44") (pintype "bidirectional"))
    )
    (net (code "62") (name "unconnected-(IC6-ADC9{slash}PB1-Pad5)") (class "Default")
      (node (ref "IC6") (pin "5") (pinfunction "ADC9/PB1_5") (pintype "bidirectional"))
    )
    (net (code "63") (name "unconnected-(IC6-AREF{slash}ADC0{slash}AC0{slash}PA0-Pad40)") (class "Default")
      (node (ref "IC6") (pin "40") (pinfunction "AREF/ADC0/AC0/PA0_40") (pintype "bidirectional"))
    )
    (net (code "64") (name "unconnected-(IC6-MOSI{slash}XCK1{slash}OD1B{slash}PD5-Pad25)") (class "Default")
      (node (ref "IC6") (pin "25") (pinfunction "MOSI/XCK1/OD1B/PD5_25") (pintype "bidirectional"))
    )
    (net (code "65") (name "unconnected-(IC6-PR0{slash}XTAL2{slash}TOSC2-Pad36)") (class "Default")
      (node (ref "IC6") (pin "36") (pinfunction "PR0/XTAL2/TOSC2_36") (pintype "passive"))
    )
    (net (code "66") (name "unconnected-(IC6-PR1{slash}XTAL1{slash}TOSC1-Pad37)") (class "Default")
      (node (ref "IC6") (pin "37") (pinfunction "PR1/XTAL1/TOSC1_37") (pintype "passive"))
    )
    (net (code "67") (name "unconnected-(IC6-SCL{slash}XCK0{slash}OC0B{slash}PE1-Pad29)") (class "Default")
      (node (ref "IC6") (pin "29") (pinfunction "SCL/XCK0/OC0B/PE1_29") (pintype "bidirectional"))
    )
    (net (code "68") (name "unconnected-(IC6-SDA{slash}OC0A{slash}PE0-Pad28)") (class "Default")
      (node (ref "IC6") (pin "28") (pinfunction "SDA/OC0A/PE0_28") (pintype "bidirectional"))
    )
    (net (code "69") (name "unconnected-(IC6-~{SS{slash}OC1A{slash}PD4}-Pad24)") (class "Default")
      (node (ref "IC6") (pin "24") (pinfunction "~{SS/OC1A/PD4}_24") (pintype "bidirectional"))
    )
  )
)
